# 380-015-113L001.net
KiCad netlist of a schematic drawn in Altium Designer
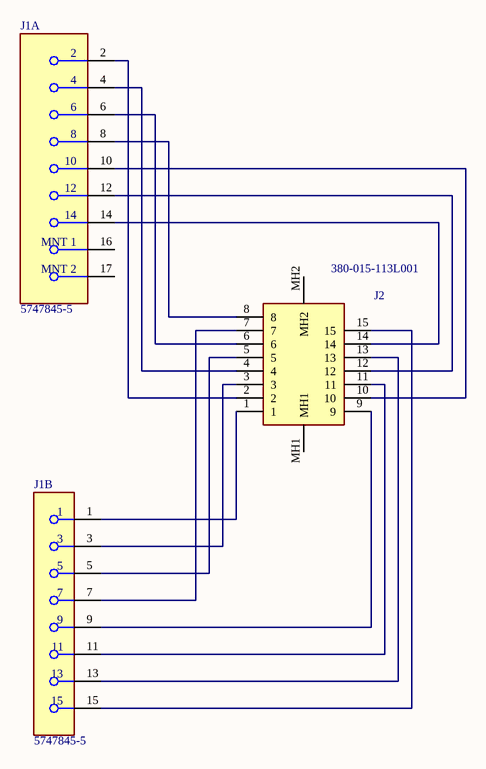
[diagram p0: 380-015-113L001.SchDoc]

(export (version "E")
  (design (tool "Eeschema 10.0.6"))
  (components
    (comp (ref "J1")
      (value "5747845-5")
      (footprint "FP-5747845-5-MFG")
      (description "CONN D-SUB RCPT 15POS R/A SOLDER")
      (fields
        (field (name "OCTOPART") "https://octopart.com/5747845-5-te+connectivity-39499908")
        (field (name "MANUFACTURER") "TE Connectivity")
      )
      (libsource (lib "Altium Content Vault") (part "e11211c69d46bddb3b0e9165465b0e6"))
    )
    (comp (ref "J2")
      (value "380-015-113L001")
      (footprint "SamacSys:380015113L001")
      (description "Connector")
      (libsource (lib "*") (part "380-015-113L001"))
    )
  )
  (nets
    (net (code "1") (name "Net-(J1-Pad1)") (class "Default")
      (node (ref "J1") (pin "1") (pinfunction "1_1") (pintype "passive"))
      (node (ref "J2") (pin "1") (pinfunction "1_1") (pintype "passive"))
    )
    (net (code "2") (name "Net-(J1-Pad2)") (class "Default")
      (node (ref "J1") (pin "2") (pinfunction "2_2") (pintype "passive"))
      (node (ref "J2") (pin "2") (pinfunction "2_2") (pintype "passive"))
    )
    (net (code "3") (name "Net-(J1-Pad3)") (class "Default")
      (node (ref "J1") (pin "3") (pinfunction "3_3") (pintype "passive"))
      (node (ref "J2") (pin "3") (pinfunction "3_3") (pintype "passive"))
    )
    (net (code "4") (name "Net-(J1-Pad4)") (class "Default")
      (node (ref "J1") (pin "4") (pinfunction "4_4") (pintype "passive"))
      (node (ref "J2") (pin "4") (pinfunction "4_4") (pintype "passive"))
    )
    (net (code "5") (name "Net-(J1-Pad5)") (class "Default")
      (node (ref "J1") (pin "5") (pinfunction "5_5") (pintype "passive"))
      (node (ref "J2") (pin "5") (pinfunction "5_5") (pintype "passive"))
    )
    (net (code "6") (name "Net-(J1-Pad6)") (class "Default")
      (node (ref "J1") (pin "6") (pinfunction "6_6") (pintype "passive"))
      (node (ref "J2") (pin "6") (pinfunction "6_6") (pintype "passive"))
    )
    (net (code "7") (name "Net-(J1-Pad7)") (class "Default")
      (node (ref "J1") (pin "7") (pinfunction "7_7") (pintype "passive"))
      (node (ref "J2") (pin "7") (pinfunction "7_7") (pintype "passive"))
    )
    (net (code "8") (name "Net-(J1-Pad8)") (class "Default")
      (node (ref "J1") (pin "8") (pinfunction "8_8") (pintype "passive"))
      (node (ref "J2") (pin "8") (pinfunction "8_8") (pintype "passive"))
    )
    (net (code "9") (name "Net-(J1-Pad9)") (class "Default")
      (node (ref "J1") (pin "9") (pinfunction "9_9") (pintype "passive"))
      (node (ref "J2") (pin "9") (pinfunction "9_9") (pintype "passive"))
    )
    (net (code "10") (name "Net-(J1-Pad10)") (class "Default")
      (node (ref "J1") (pin "10") (pinfunction "10_10") (pintype "passive"))
      (node (ref "J2") (pin "10") (pinfunction "10_10") (pintype "passive"))
    )
    (net (code "11") (name "Net-(J1-Pad11)") (class "Default")
      (node (ref "J1") (pin "11") (pinfunction "11_11") (pintype "passive"))
      (node (ref "J2") (pin "11") (pinfunction "11_11") (pintype "passive"))
    )
    (net (code "12") (name "Net-(J1-Pad12)") (class "Default")
      (node (ref "J1") (pin "12") (pinfunction "12_12") (pintype "passive"))
      (node (ref "J2") (pin "12") (pinfunction "12_12") (pintype "passive"))
    )
    (net (code "13") (name "Net-(J1-Pad13)") (class "Default")
      (node (ref "J1") (pin "13") (pinfunction "13_13") (pintype "passive"))
      (node (ref "J2") (pin "13") (pinfunction "13_13") (pintype "passive"))
    )
    (net (code "14") (name "Net-(J1-Pad14)") (class "Default")
      (node (ref "J1") (pin "14") (pinfunction "14_14") (pintype "passive"))
      (node (ref "J2") (pin "14") (pinfunction "14_14") (pintype "passive"))
    )
    (net (code "15") (name "Net-(J1-Pad15)") (class "Default")
      (node (ref "J1") (pin "15") (pinfunction "15_15") (pintype "passive"))
      (node (ref "J2") (pin "15") (pinfunction "15_15") (pintype "passive"))
    )
    (net (code "16") (name "unconnected-(J1A-MNT_1-Pad16)") (class "Default")
      (node (ref "J1") (pin "16") (pinfunction "MNT_1_16") (pintype "passive"))
    )
    (net (code "17") (name "unconnected-(J1A-MNT_2-Pad17)") (class "Default")
      (node (ref "J1") (pin "17") (pinfunction "MNT_2_17") (pintype "passive"))
    )
    (net (code "18") (name "unconnected-(J2-PadMH1)") (class "Default")
      (node (ref "J2") (pin "MH1") (pinfunction "MH1_MH1") (pintype "passive"))
    )
    (net (code "19") (name "unconnected-(J2-PadMH2)") (class "Default")
      (node (ref "J2") (pin "MH2") (pinfunction "MH2_MH2") (pintype "passive"))
    )
  )
)
